# ov7670.net
KiCad netlist of a schematic drawn in Altium Designer
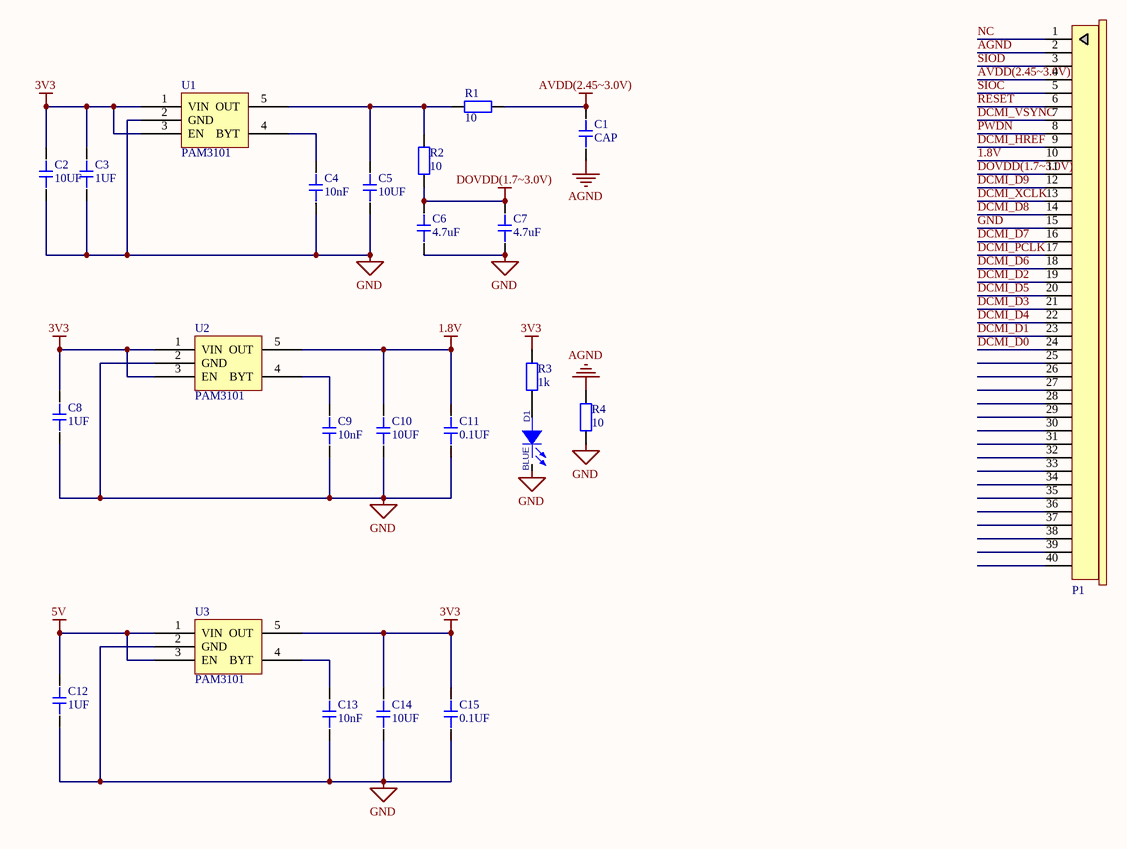
[diagram p0: ov7670电路（骑飞）.SchDoc]

(export (version "E")
  (design (tool "Eeschema 10.0.6"))
  (components
    (comp (ref "C1") (value "CAP") (footprint "C_0603") (libsource (lib "XJDYJB-v1.24") (part "CAP")))
    (comp (ref "C2") (value "10UF") (footprint "C_0805") (libsource (lib "XJDYJB-v1.24") (part "CAP")))
    (comp (ref "C3") (value "1UF") (footprint "C_0603") (libsource (lib "XJDYJB-v1.24") (part "CAP")))
    (comp (ref "C4") (value "10nF") (footprint "C_0603") (libsource (lib "XJDYJB-v1.24") (part "CAP")))
    (comp (ref "C5") (value "10UF") (footprint "C_0805") (libsource (lib "XJDYJB-v1.24") (part "CAP")))
    (comp (ref "C6") (value "4.7uF") (footprint "C_0805") (libsource (lib "XJDYJB-v1.24") (part "CAP")))
    (comp (ref "C7") (value "4.7uF") (footprint "C_0603") (libsource (lib "XJDYJB-v1.24") (part "CAP")))
    (comp (ref "C8") (value "1UF") (footprint "C_0603") (libsource (lib "XJDYJB-v1.24") (part "CAP")))
    (comp (ref "C9") (value "10nF") (footprint "C_0603") (libsource (lib "XJDYJB-v1.24") (part "CAP")))
    (comp (ref "C10") (value "10UF") (footprint "C_0805") (libsource (lib "XJDYJB-v1.24") (part "CAP")))
    (comp (ref "C11") (value "0.1UF") (footprint "C_0603") (libsource (lib "XJDYJB-v1.24") (part "CAP")))
    (comp (ref "C12") (value "1UF") (footprint "C_0603") (libsource (lib "XJDYJB-v1.24") (part "CAP")))
    (comp (ref "C13") (value "10nF") (footprint "C_0603") (libsource (lib "XJDYJB-v1.24") (part "CAP")))
    (comp (ref "C14") (value "10UF") (footprint "C_0805") (libsource (lib "XJDYJB-v1.24") (part "CAP")))
    (comp (ref "C15") (value "0.1UF") (footprint "C_0603") (libsource (lib "XJDYJB-v1.24") (part "CAP")))
    (comp (ref "D1")
      (value "BLUE")
      (footprint "LED_0603")
      (fields (field (name "Comment") "LED"))
      (libsource (lib "XJDYJB-v1.24") (part "LED"))
    )
    (comp (ref "P1")
      (value "FPC")
      (footprint "FPC0.5-40P-A")
      (description "FPC排线连接器")
      (libsource (lib "HDR_Fszhang") (part "FPC-40P"))
    )
    (comp (ref "R1")
      (value "10")
      (footprint "0603-1")
      (description "贴片电阻")
      (fields (field (name "Comment") "Res1") (field (name "PUBLISHER") "Altium Limited"))
      (libsource (lib "") (part "Res1_1"))
    )
    (comp (ref "R2")
      (value "10")
      (footprint "0603-1")
      (description "贴片电阻")
      (fields (field (name "Comment") "Res1") (field (name "PUBLISHER") "Altium Limited"))
      (libsource (lib "Fszhang") (part "Res1"))
    )
    (comp (ref "R3")
      (value "1k")
      (footprint "0603-1")
      (description "贴片电阻")
      (fields (field (name "Comment") "Res1") (field (name "PUBLISHER") "Altium Limited"))
      (libsource (lib "Fszhang") (part "Res1"))
    )
    (comp (ref "R4")
      (value "10")
      (footprint "0603-1")
      (description "贴片电阻")
      (fields (field (name "Comment") "Res1") (field (name "PUBLISHER") "Altium Limited"))
      (libsource (lib "Fszhang") (part "Res1"))
    )
    (comp (ref "U1")
      (value "PAM3101")
      (footprint "SOT23-5")
      (description "LDO")
      (libsource (lib "XJDYJB-v1.21") (part "PAM3101"))
    )
    (comp (ref "U2")
      (value "PAM3101")
      (footprint "SOT23-5")
      (description "LDO")
      (libsource (lib "XJDYJB-v1.21") (part "PAM3101"))
    )
    (comp (ref "U3")
      (value "PAM3101")
      (footprint "SOT23-5")
      (description "LDO")
      (libsource (lib "XJDYJB-v1.21") (part "PAM3101"))
    )
  )
  (nets
    (net (code "1") (name "/DCMI_D0") (class "Default")
      (node (ref "P1") (pin "24") (pinfunction "24_24") (pintype "passive"))
    )
    (net (code "2") (name "/DCMI_D1") (class "Default")
      (node (ref "P1") (pin "23") (pinfunction "23_23") (pintype "passive"))
    )
    (net (code "3") (name "/DCMI_D2") (class "Default")
      (node (ref "P1") (pin "19") (pinfunction "19_19") (pintype "passive"))
    )
    (net (code "4") (name "/DCMI_D3") (class "Default")
      (node (ref "P1") (pin "21") (pinfunction "21_21") (pintype "passive"))
    )
    (net (code "5") (name "/DCMI_D4") (class "Default")
      (node (ref "P1") (pin "22") (pinfunction "22_22") (pintype "passive"))
    )
    (net (code "6") (name "/DCMI_D5") (class "Default")
      (node (ref "P1") (pin "20") (pinfunction "20_20") (pintype "passive"))
    )
    (net (code "7") (name "/DCMI_D6") (class "Default")
      (node (ref "P1") (pin "18") (pinfunction "18_18") (pintype "passive"))
    )
    (net (code "8") (name "/DCMI_D7") (class "Default")
      (node (ref "P1") (pin "16") (pinfunction "16_16") (pintype "passive"))
    )
    (net (code "9") (name "/DCMI_D8") (class "Default")
      (node (ref "P1") (pin "14") (pinfunction "14_14") (pintype "passive"))
    )
    (net (code "10") (name "/DCMI_D9") (class "Default")
      (node (ref "P1") (pin "12") (pinfunction "12_12") (pintype "passive"))
    )
    (net (code "11") (name "/DCMI_HREF") (class "Default")
      (node (ref "P1") (pin "9") (pinfunction "9_9") (pintype "passive"))
    )
    (net (code "12") (name "/DCMI_PCLK") (class "Default")
      (node (ref "P1") (pin "17") (pinfunction "17_17") (pintype "passive"))
    )
    (net (code "13") (name "/DCMI_VSYNC") (class "Default")
      (node (ref "P1") (pin "7") (pinfunction "7_7") (pintype "passive"))
    )
    (net (code "14") (name "/DCMI_XCLK") (class "Default")
      (node (ref "P1") (pin "13") (pinfunction "13_13") (pintype "passive"))
    )
    (net (code "15") (name "/NC") (class "Default")
      (node (ref "P1") (pin "1") (pinfunction "1_1") (pintype "passive"))
    )
    (net (code "16") (name "/PWDN") (class "Default")
      (node (ref "P1") (pin "8") (pinfunction "8_8") (pintype "passive"))
    )
    (net (code "17") (name "/RESET") (class "Default")
      (node (ref "P1") (pin "6") (pinfunction "6_6") (pintype "passive"))
    )
    (net (code "18") (name "/SIOC") (class "Default")
      (node (ref "P1") (pin "5") (pinfunction "5_5") (pintype "passive"))
    )
    (net (code "19") (name "/SIOD") (class "Default")
      (node (ref "P1") (pin "3") (pinfunction "3_3") (pintype "passive"))
    )
    (net (code "20") (name "1.8V") (class "Default")
      (node (ref "C10") (pin "2") (pinfunction "2_2") (pintype "passive"))
      (node (ref "C11") (pin "2") (pinfunction "2_2") (pintype "passive"))
      (node (ref "P1") (pin "10") (pinfunction "10_10") (pintype "passive"))
      (node (ref "U2") (pin "5") (pinfunction "OUT_5") (pintype "passive"))
    )
    (net (code "21") (name "3V3") (class "Default")
      (node (ref "C14") (pin "2") (pinfunction "2_2") (pintype "passive"))
      (node (ref "C15") (pin "2") (pinfunction "2_2") (pintype "passive"))
      (node (ref "C2") (pin "2") (pinfunction "2_2") (pintype "passive"))
      (node (ref "C3") (pin "2") (pinfunction "2_2") (pintype "passive"))
      (node (ref "C8") (pin "2") (pinfunction "2_2") (pintype "passive"))
      (node (ref "R3") (pin "2") (pinfunction "2_2") (pintype "passive"))
      (node (ref "U1") (pin "1") (pinfunction "VIN_1") (pintype "passive"))
      (node (ref "U1") (pin "3") (pinfunction "EN_3") (pintype "passive"))
      (node (ref "U2") (pin "1") (pinfunction "VIN_1") (pintype "passive"))
      (node (ref "U2") (pin "3") (pinfunction "EN_3") (pintype "passive"))
      (node (ref "U3") (pin "5") (pinfunction "OUT_5") (pintype "passive"))
    )
    (net (code "22") (name "5V") (class "Default")
      (node (ref "C12") (pin "2") (pinfunction "2_2") (pintype "passive"))
      (node (ref "U3") (pin "1") (pinfunction "VIN_1") (pintype "passive"))
      (node (ref "U3") (pin "3") (pinfunction "EN_3") (pintype "passive"))
    )
    (net (code "23") (name "AGND") (class "Default")
      (node (ref "C1") (pin "1") (pinfunction "1_1") (pintype "passive"))
      (node (ref "P1") (pin "2") (pinfunction "2_2") (pintype "passive"))
      (node (ref "R4") (pin "2") (pinfunction "2_2") (pintype "passive"))
    )
    (net (code "24") (name "AVDD(2.45~3.0V)") (class "Default")
      (node (ref "C1") (pin "2") (pinfunction "2_2") (pintype "passive"))
      (node (ref "P1") (pin "4") (pinfunction "4_4") (pintype "passive"))
      (node (ref "R1") (pin "2") (pinfunction "2_2") (pintype "passive"))
    )
    (net (code "25") (name "DOVDD(1.7~3.0V)") (class "Default")
      (node (ref "C6") (pin "2") (pinfunction "2_2") (pintype "passive"))
      (node (ref "C7") (pin "2") (pinfunction "2_2") (pintype "passive"))
      (node (ref "P1") (pin "11") (pinfunction "11_11") (pintype "passive"))
      (node (ref "R2") (pin "1") (pinfunction "1_1") (pintype "passive"))
    )
    (net (code "26") (name "GND") (class "Default")
      (node (ref "C10") (pin "1") (pinfunction "1_1") (pintype "passive"))
      (node (ref "C11") (pin "1") (pinfunction "1_1") (pintype "passive"))
      (node (ref "C12") (pin "1") (pinfunction "1_1") (pintype "passive"))
      (node (ref "C13") (pin "1") (pinfunction "1_1") (pintype "passive"))
      (node (ref "C14") (pin "1") (pinfunction "1_1") (pintype "passive"))
      (node (ref "C15") (pin "1") (pinfunction "1_1") (pintype "passive"))
      (node (ref "C2") (pin "1") (pinfunction "1_1") (pintype "passive"))
      (node (ref "C3") (pin "1") (pinfunction "1_1") (pintype "passive"))
      (node (ref "C4") (pin "1") (pinfunction "1_1") (pintype "passive"))
      (node (ref "C5") (pin "1") (pinfunction "1_1") (pintype "passive"))
      (node (ref "C6") (pin "1") (pinfunction "1_1") (pintype "passive"))
      (node (ref "C7") (pin "1") (pinfunction "1_1") (pintype "passive"))
      (node (ref "C8") (pin "1") (pinfunction "1_1") (pintype "passive"))
      (node (ref "C9") (pin "1") (pinfunction "1_1") (pintype "passive"))
      (node (ref "D1") (pin "2") (pinfunction "CATHODE_2") (pintype "passive"))
      (node (ref "P1") (pin "15") (pinfunction "15_15") (pintype "passive"))
      (node (ref "R4") (pin "1") (pinfunction "1_1") (pintype "passive"))
      (node (ref "U1") (pin "2") (pinfunction "GND_2") (pintype "passive"))
      (node (ref "U2") (pin "2") (pinfunction "GND_2") (pintype "passive"))
      (node (ref "U3") (pin "2") (pinfunction "GND_2") (pintype "passive"))
    )
    (net (code "27") (name "Net-(D1-ANODE)") (class "Default")
      (node (ref "D1") (pin "1") (pinfunction "ANODE_1") (pintype "passive"))
      (node (ref "R3") (pin "1") (pinfunction "1_1") (pintype "passive"))
    )
    (net (code "28") (name "Net-(U1-BYT)") (class "Default")
      (node (ref "C4") (pin "2") (pinfunction "2_2") (pintype "passive"))
      (node (ref "U1") (pin "4") (pinfunction "BYT_4") (pintype "passive"))
    )
    (net (code "29") (name "Net-(U1-OUT)") (class "Default")
      (node (ref "C5") (pin "2") (pinfunction "2_2") (pintype "passive"))
      (node (ref "R1") (pin "1") (pinfunction "1_1") (pintype "passive"))
      (node (ref "R2") (pin "2") (pinfunction "2_2") (pintype "passive"))
      (node (ref "U1") (pin "5") (pinfunction "OUT_5") (pintype "passive"))
    )
    (net (code "30") (name "Net-(U2-BYT)") (class "Default")
      (node (ref "C9") (pin "2") (pinfunction "2_2") (pintype "passive"))
      (node (ref "U2") (pin "4") (pinfunction "BYT_4") (pintype "passive"))
    )
    (net (code "31") (name "Net-(U3-BYT)") (class "Default")
      (node (ref "C13") (pin "2") (pinfunction "2_2") (pintype "passive"))
      (node (ref "U3") (pin "4") (pinfunction "BYT_4") (pintype "passive"))
    )
    (net (code "32") (name "unconnected-(P1-Pad25)") (class "Default")
      (node (ref "P1") (pin "25") (pinfunction "25_25") (pintype "passive"))
    )
    (net (code "33") (name "unconnected-(P1-Pad26)") (class "Default")
      (node (ref "P1") (pin "26") (pinfunction "26_26") (pintype "passive"))
    )
    (net (code "34") (name "unconnected-(P1-Pad27)") (class "Default")
      (node (ref "P1") (pin "27") (pinfunction "27_27") (pintype "passive"))
    )
    (net (code "35") (name "unconnected-(P1-Pad28)") (class "Default")
      (node (ref "P1") (pin "28") (pinfunction "28_28") (pintype "passive"))
    )
    (net (code "36") (name "unconnected-(P1-Pad29)") (class "Default")
      (node (ref "P1") (pin "29") (pinfunction "29_29") (pintype "passive"))
    )
    (net (code "37") (name "unconnected-(P1-Pad30)") (class "Default")
      (node (ref "P1") (pin "30") (pinfunction "30_30") (pintype "passive"))
    )
    (net (code "38") (name "unconnected-(P1-Pad31)") (class "Default")
      (node (ref "P1") (pin "31") (pinfunction "31_31") (pintype "passive"))
    )
    (net (code "39") (name "unconnected-(P1-Pad32)") (class "Default")
      (node (ref "P1") (pin "32") (pinfunction "32_32") (pintype "passive"))
    )
    (net (code "40") (name "unconnected-(P1-Pad33)") (class "Default")
      (node (ref "P1") (pin "33") (pinfunction "33_33") (pintype "passive"))
    )
    (net (code "41") (name "unconnected-(P1-Pad34)") (class "Default")
      (node (ref "P1") (pin "34") (pinfunction "34_34") (pintype "passive"))
    )
    (net (code "42") (name "unconnected-(P1-Pad35)") (class "Default")
      (node (ref "P1") (pin "35") (pinfunction "35_35") (pintype "passive"))
    )
    (net (code "43") (name "unconnected-(P1-Pad36)") (class "Default")
      (node (ref "P1") (pin "36") (pinfunction "36_36") (pintype "passive"))
    )
    (net (code "44") (name "unconnected-(P1-Pad37)") (class "Default")
      (node (ref "P1") (pin "37") (pinfunction "37_37") (pintype "passive"))
    )
    (net (code "45") (name "unconnected-(P1-Pad38)") (class "Default")
      (node (ref "P1") (pin "38") (pinfunction "38_38") (pintype "passive"))
    )
    (net (code "46") (name "unconnected-(P1-Pad39)") (class "Default")
      (node (ref "P1") (pin "39") (pinfunction "39_39") (pintype "passive"))
    )
    (net (code "47") (name "unconnected-(P1-Pad40)") (class "Default")
      (node (ref "P1") (pin "40") (pinfunction "40_40") (pintype "passive"))
    )
  )
)
